# untitled.net
KiCad netlist of a schematic drawn in EAGLE
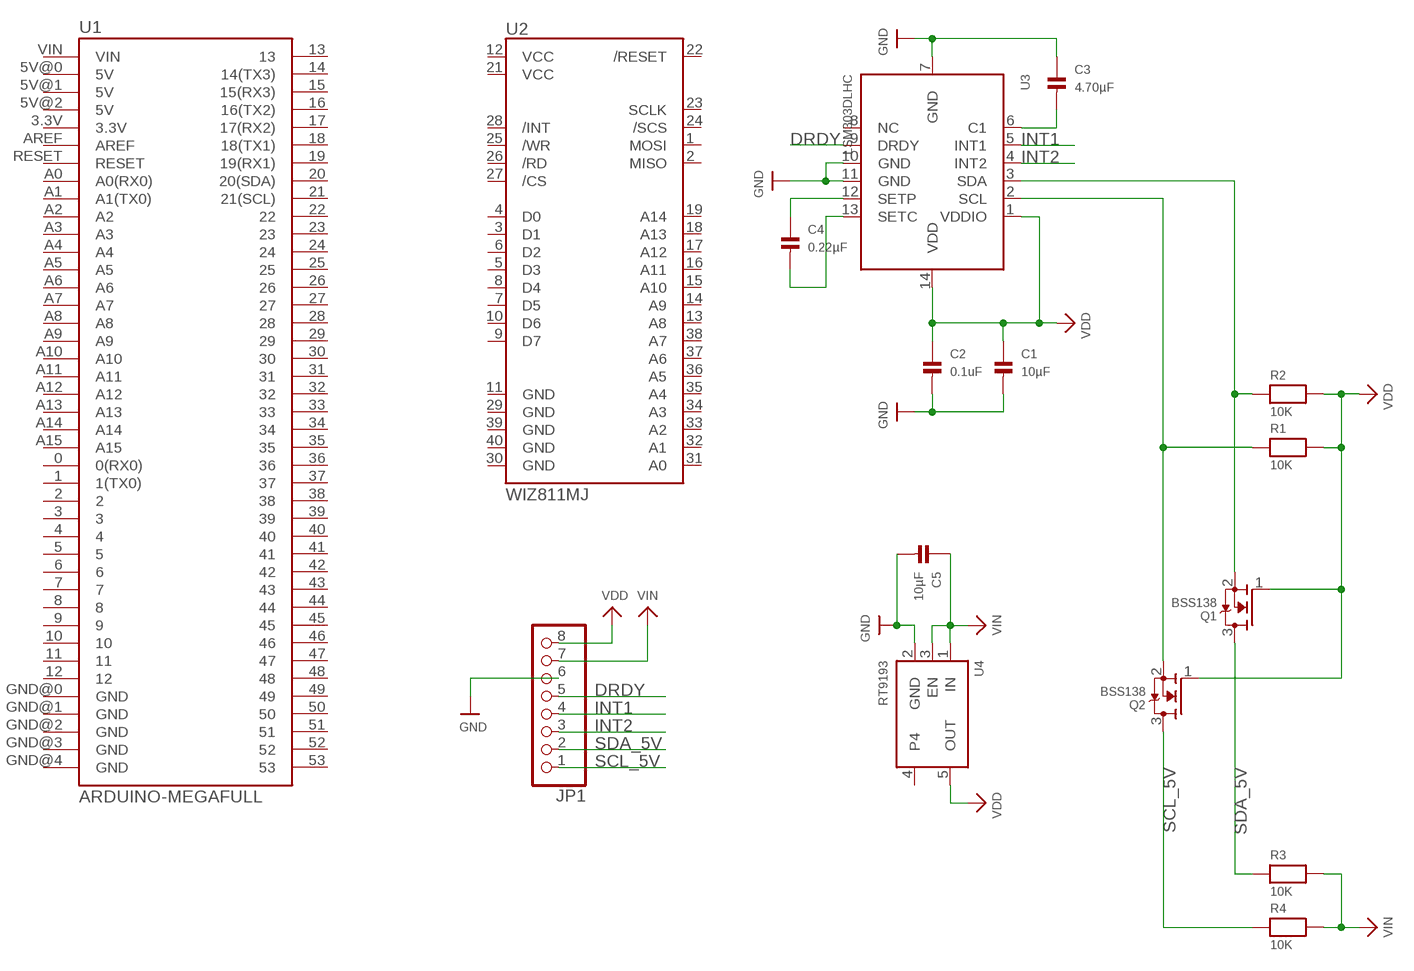
[diagram p0: schematic, sheet 1]

(export (version "E")
  (design (tool "Eeschema 10.0.6"))
  (components
    (comp (ref "C1")
      (value "10µF")
      (footprint "eagle-import:_0805")
      (libsource (lib "eagle-import") (part "CAP_CERAMIC_0805"))
    )
    (comp (ref "C2")
      (value "0.1uF")
      (footprint "eagle-import:_0805")
      (libsource (lib "eagle-import") (part "CAP_CERAMIC_0805"))
    )
    (comp (ref "C3")
      (value "4.70µF")
      (footprint "eagle-import:_0805")
      (libsource (lib "eagle-import") (part "CAP_CERAMIC_0805"))
    )
    (comp (ref "C4")
      (value "0.22µF")
      (footprint "eagle-import:_0805")
      (libsource (lib "eagle-import") (part "CAP_CERAMIC_0805"))
    )
    (comp (ref "C5")
      (value "10µF")
      (footprint "eagle-import:_0805")
      (libsource (lib "eagle-import") (part "CAP_CERAMIC_0805"))
    )
    (comp (ref "JP1")
      (value "HEADER-1X876MIL")
      (footprint "eagle-import:1X08_ROUND_76")
      (libsource (lib "eagle-import") (part "HEADER-1X876MIL"))
    )
    (comp (ref "Q1")
      (value "BSS138")
      (footprint "eagle-import:SOT23-WIDE")
      (libsource (lib "eagle-import") (part "MOSFET-NWIDE"))
    )
    (comp (ref "Q2")
      (value "BSS138")
      (footprint "eagle-import:SOT23-WIDE")
      (libsource (lib "eagle-import") (part "MOSFET-NWIDE"))
    )
    (comp (ref "R1")
      (value "10K")
      (footprint "eagle-import:_0805")
      (libsource (lib "eagle-import") (part "RESISTOR_0805"))
    )
    (comp (ref "R2")
      (value "10K")
      (footprint "eagle-import:_0805")
      (libsource (lib "eagle-import") (part "RESISTOR_0805"))
    )
    (comp (ref "R3")
      (value "10K")
      (footprint "eagle-import:_0805")
      (libsource (lib "eagle-import") (part "RESISTOR_0805"))
    )
    (comp (ref "R4")
      (value "10K")
      (footprint "eagle-import:_0805")
      (libsource (lib "eagle-import") (part "RESISTOR_0805"))
    )
    (comp (ref "U1")
      (value "ARDUINO-MEGAFULL")
      (footprint "eagle-import:ARDUINO_MEGA")
      (libsource (lib "eagle-import") (part "ARDUINO-MEGAFULL"))
    )
    (comp (ref "U2")
      (value "WIZ811MJ")
      (footprint "eagle-import:WIZ811MJ")
      (libsource (lib "eagle-import") (part "WIZ811MJ"))
    )
    (comp (ref "U3")
      (value "LSM303DLHC")
      (footprint "eagle-import:LGA14")
      (libsource (lib "eagle-import") (part "LSM303DLHC"))
    )
    (comp (ref "U4")
      (value "RT9193")
      (footprint "eagle-import:SOT23-5")
      (libsource (lib "eagle-import") (part "VREG_SOT23-5"))
    )
  )
  (nets
    (net (code "1") (name "/DRDY") (class "Default")
      (node (ref "JP1") (pin "5") (pinfunction "5_5") (pintype "passive"))
      (node (ref "U3") (pin "9") (pinfunction "DRDY_9") (pintype "output"))
    )
    (net (code "2") (name "/INT1") (class "Default")
      (node (ref "JP1") (pin "4") (pinfunction "4_4") (pintype "passive"))
      (node (ref "U3") (pin "5") (pinfunction "INT1_5") (pintype "output"))
    )
    (net (code "3") (name "/INT2") (class "Default")
      (node (ref "JP1") (pin "3") (pinfunction "3_3") (pintype "passive"))
      (node (ref "U3") (pin "4") (pinfunction "INT2_4") (pintype "output"))
    )
    (net (code "4") (name "/SCL_5V") (class "Default")
      (node (ref "JP1") (pin "1") (pinfunction "1_1") (pintype "passive"))
      (node (ref "Q2") (pin "3") (pinfunction "D_3") (pintype "bidirectional"))
      (node (ref "R4") (pin "1") (pinfunction "1_1") (pintype "passive"))
    )
    (net (code "5") (name "/SDA_5V") (class "Default")
      (node (ref "JP1") (pin "2") (pinfunction "2_2") (pintype "passive"))
      (node (ref "Q1") (pin "3") (pinfunction "D_3") (pintype "bidirectional"))
      (node (ref "R3") (pin "1") (pinfunction "1_1") (pintype "passive"))
    )
    (net (code "6") (name "GND") (class "Default")
      (node (ref "C1") (pin "2") (pinfunction "P$2_2") (pintype "passive"))
      (node (ref "C2") (pin "2") (pinfunction "P$2_2") (pintype "passive"))
      (node (ref "C3") (pin "1") (pinfunction "P$1_1") (pintype "passive"))
      (node (ref "C5") (pin "2") (pinfunction "P$2_2") (pintype "passive"))
      (node (ref "JP1") (pin "6") (pinfunction "6_6") (pintype "passive"))
      (node (ref "U3") (pin "10") (pinfunction "GND_10") (pintype "power_in"))
      (node (ref "U3") (pin "11") (pinfunction "GND_11") (pintype "power_in"))
      (node (ref "U3") (pin "7") (pinfunction "GND_7") (pintype "power_in"))
      (node (ref "U4") (pin "2") (pinfunction "GND_2") (pintype "bidirectional"))
    )
    (net (code "7") (name "Net-(C3-P$2)") (class "Default")
      (node (ref "C3") (pin "2") (pinfunction "P$2_2") (pintype "passive"))
      (node (ref "U3") (pin "6") (pinfunction "C1_6") (pintype "bidirectional"))
    )
    (net (code "8") (name "Net-(C4-P$1)") (class "Default")
      (node (ref "C4") (pin "1") (pinfunction "P$1_1") (pintype "passive"))
      (node (ref "U3") (pin "12") (pinfunction "SETP_12") (pintype "bidirectional"))
    )
    (net (code "9") (name "Net-(C4-P$2)") (class "Default")
      (node (ref "C4") (pin "2") (pinfunction "P$2_2") (pintype "passive"))
      (node (ref "U3") (pin "13") (pinfunction "SETC_13") (pintype "bidirectional"))
    )
    (net (code "10") (name "Net-(Q1-S)") (class "Default")
      (node (ref "Q1") (pin "2") (pinfunction "S_2") (pintype "bidirectional"))
      (node (ref "R2") (pin "1") (pinfunction "1_1") (pintype "passive"))
      (node (ref "U3") (pin "3") (pinfunction "SDA_3") (pintype "bidirectional"))
    )
    (net (code "11") (name "Net-(Q2-S)") (class "Default")
      (node (ref "Q2") (pin "2") (pinfunction "S_2") (pintype "bidirectional"))
      (node (ref "R1") (pin "1") (pinfunction "1_1") (pintype "passive"))
      (node (ref "U3") (pin "2") (pinfunction "SCL_2") (pintype "bidirectional"))
    )
    (net (code "12") (name "VDD") (class "Default")
      (node (ref "C1") (pin "1") (pinfunction "P$1_1") (pintype "passive"))
      (node (ref "C2") (pin "1") (pinfunction "P$1_1") (pintype "passive"))
      (node (ref "JP1") (pin "8") (pinfunction "8_8") (pintype "passive"))
      (node (ref "Q1") (pin "1") (pinfunction "G_1") (pintype "bidirectional"))
      (node (ref "Q2") (pin "1") (pinfunction "G_1") (pintype "bidirectional"))
      (node (ref "R1") (pin "2") (pinfunction "2_2") (pintype "passive"))
      (node (ref "R2") (pin "2") (pinfunction "2_2") (pintype "passive"))
      (node (ref "U3") (pin "1") (pinfunction "VDDIO_1") (pintype "power_in"))
      (node (ref "U3") (pin "14") (pinfunction "VDD_14") (pintype "power_in"))
      (node (ref "U4") (pin "5") (pinfunction "OUT_5") (pintype "bidirectional"))
    )
    (net (code "13") (name "VIN") (class "Default")
      (node (ref "C5") (pin "1") (pinfunction "P$1_1") (pintype "passive"))
      (node (ref "JP1") (pin "7") (pinfunction "7_7") (pintype "passive"))
      (node (ref "R3") (pin "2") (pinfunction "2_2") (pintype "passive"))
      (node (ref "R4") (pin "2") (pinfunction "2_2") (pintype "passive"))
      (node (ref "U4") (pin "1") (pinfunction "IN_1") (pintype "bidirectional"))
      (node (ref "U4") (pin "3") (pinfunction "EN_3") (pintype "bidirectional"))
    )
    (net (code "14") (name "unconnected-(U1-0(RX0)-Pad0)") (class "Default")
      (node (ref "U1") (pin "0") (pinfunction "0(RX0)_0") (pintype "bidirectional"))
    )
    (net (code "15") (name "unconnected-(U1-1(TX0)-Pad1)") (class "Default")
      (node (ref "U1") (pin "1") (pinfunction "1(TX0)_1") (pintype "bidirectional"))
    )
    (net (code "16") (name "unconnected-(U1-5V-Pad5V@0)") (class "Default")
      (node (ref "U1") (pin "5V@0") (pinfunction "5V_5V@0") (pintype "bidirectional"))
    )
    (net (code "17") (name "unconnected-(U1-5V-Pad5V@1)") (class "Default")
      (node (ref "U1") (pin "5V@1") (pinfunction "5V_5V@1") (pintype "bidirectional"))
    )
    (net (code "18") (name "unconnected-(U1-5V-Pad5V@2)") (class "Default")
      (node (ref "U1") (pin "5V@2") (pinfunction "5V_5V@2") (pintype "bidirectional"))
    )
    (net (code "19") (name "unconnected-(U1-14(TX3)-Pad14)") (class "Default")
      (node (ref "U1") (pin "14") (pinfunction "14(TX3)_14") (pintype "bidirectional"))
    )
    (net (code "20") (name "unconnected-(U1-15(RX3)-Pad15)") (class "Default")
      (node (ref "U1") (pin "15") (pinfunction "15(RX3)_15") (pintype "bidirectional"))
    )
    (net (code "21") (name "unconnected-(U1-16(TX2)-Pad16)") (class "Default")
      (node (ref "U1") (pin "16") (pinfunction "16(TX2)_16") (pintype "bidirectional"))
    )
    (net (code "22") (name "unconnected-(U1-17(RX2)-Pad17)") (class "Default")
      (node (ref "U1") (pin "17") (pinfunction "17(RX2)_17") (pintype "bidirectional"))
    )
    (net (code "23") (name "unconnected-(U1-18(TX1)-Pad18)") (class "Default")
      (node (ref "U1") (pin "18") (pinfunction "18(TX1)_18") (pintype "bidirectional"))
    )
    (net (code "24") (name "unconnected-(U1-19(RX1)-Pad19)") (class "Default")
      (node (ref "U1") (pin "19") (pinfunction "19(RX1)_19") (pintype "bidirectional"))
    )
    (net (code "25") (name "unconnected-(U1-20(SDA)-Pad20)") (class "Default")
      (node (ref "U1") (pin "20") (pinfunction "20(SDA)_20") (pintype "bidirectional"))
    )
    (net (code "26") (name "unconnected-(U1-21(SCL)-Pad21)") (class "Default")
      (node (ref "U1") (pin "21") (pinfunction "21(SCL)_21") (pintype "bidirectional"))
    )
    (net (code "27") (name "unconnected-(U1-A0(RX0)-PadA0)") (class "Default")
      (node (ref "U1") (pin "A0") (pinfunction "A0(RX0)_A0") (pintype "bidirectional"))
    )
    (net (code "28") (name "unconnected-(U1-A1(TX0)-PadA1)") (class "Default")
      (node (ref "U1") (pin "A1") (pinfunction "A1(TX0)_A1") (pintype "bidirectional"))
    )
    (net (code "29") (name "unconnected-(U1-GND-PadGND@0)") (class "Default")
      (node (ref "U1") (pin "GND@0") (pinfunction "GND_GND@0") (pintype "bidirectional"))
    )
    (net (code "30") (name "unconnected-(U1-GND-PadGND@1)") (class "Default")
      (node (ref "U1") (pin "GND@1") (pinfunction "GND_GND@1") (pintype "bidirectional"))
    )
    (net (code "31") (name "unconnected-(U1-GND-PadGND@2)") (class "Default")
      (node (ref "U1") (pin "GND@2") (pinfunction "GND_GND@2") (pintype "bidirectional"))
    )
    (net (code "32") (name "unconnected-(U1-GND-PadGND@3)") (class "Default")
      (node (ref "U1") (pin "GND@3") (pinfunction "GND_GND@3") (pintype "bidirectional"))
    )
    (net (code "33") (name "unconnected-(U1-GND-PadGND@4)") (class "Default")
      (node (ref "U1") (pin "GND@4") (pinfunction "GND_GND@4") (pintype "bidirectional"))
    )
    (net (code "34") (name "unconnected-(U1-Pad2)") (class "Default")
      (node (ref "U1") (pin "2") (pinfunction "2_2") (pintype "bidirectional"))
    )
    (net (code "35") (name "unconnected-(U1-Pad3)") (class "Default")
      (node (ref "U1") (pin "3") (pinfunction "3_3") (pintype "bidirectional"))
    )
    (net (code "36") (name "unconnected-(U1-Pad3.3V)") (class "Default")
      (node (ref "U1") (pin "3.3V") (pinfunction "3.3V_3.3V") (pintype "bidirectional"))
    )
    (net (code "37") (name "unconnected-(U1-Pad4)") (class "Default")
      (node (ref "U1") (pin "4") (pinfunction "4_4") (pintype "bidirectional"))
    )
    (net (code "38") (name "unconnected-(U1-Pad5)") (class "Default")
      (node (ref "U1") (pin "5") (pinfunction "5_5") (pintype "bidirectional"))
    )
    (net (code "39") (name "unconnected-(U1-Pad6)") (class "Default")
      (node (ref "U1") (pin "6") (pinfunction "6_6") (pintype "bidirectional"))
    )
    (net (code "40") (name "unconnected-(U1-Pad7)") (class "Default")
      (node (ref "U1") (pin "7") (pinfunction "7_7") (pintype "bidirectional"))
    )
    (net (code "41") (name "unconnected-(U1-Pad8)") (class "Default")
      (node (ref "U1") (pin "8") (pinfunction "8_8") (pintype "bidirectional"))
    )
    (net (code "42") (name "unconnected-(U1-Pad9)") (class "Default")
      (node (ref "U1") (pin "9") (pinfunction "9_9") (pintype "bidirectional"))
    )
    (net (code "43") (name "unconnected-(U1-Pad10)") (class "Default")
      (node (ref "U1") (pin "10") (pinfunction "10_10") (pintype "bidirectional"))
    )
    (net (code "44") (name "unconnected-(U1-Pad11)") (class "Default")
      (node (ref "U1") (pin "11") (pinfunction "11_11") (pintype "bidirectional"))
    )
    (net (code "45") (name "unconnected-(U1-Pad12)") (class "Default")
      (node (ref "U1") (pin "12") (pinfunction "12_12") (pintype "bidirectional"))
    )
    (net (code "46") (name "unconnected-(U1-Pad13)") (class "Default")
      (node (ref "U1") (pin "13") (pinfunction "13_13") (pintype "bidirectional"))
    )
    (net (code "47") (name "unconnected-(U1-Pad22)") (class "Default")
      (node (ref "U1") (pin "22") (pinfunction "22_22") (pintype "bidirectional"))
    )
    (net (code "48") (name "unconnected-(U1-Pad23)") (class "Default")
      (node (ref "U1") (pin "23") (pinfunction "23_23") (pintype "bidirectional"))
    )
    (net (code "49") (name "unconnected-(U1-Pad24)") (class "Default")
      (node (ref "U1") (pin "24") (pinfunction "24_24") (pintype "bidirectional"))
    )
    (net (code "50") (name "unconnected-(U1-Pad25)") (class "Default")
      (node (ref "U1") (pin "25") (pinfunction "25_25") (pintype "bidirectional"))
    )
    (net (code "51") (name "unconnected-(U1-Pad26)") (class "Default")
      (node (ref "U1") (pin "26") (pinfunction "26_26") (pintype "bidirectional"))
    )
    (net (code "52") (name "unconnected-(U1-Pad27)") (class "Default")
      (node (ref "U1") (pin "27") (pinfunction "27_27") (pintype "bidirectional"))
    )
    (net (code "53") (name "unconnected-(U1-Pad28)") (class "Default")
      (node (ref "U1") (pin "28") (pinfunction "28_28") (pintype "bidirectional"))
    )
    (net (code "54") (name "unconnected-(U1-Pad29)") (class "Default")
      (node (ref "U1") (pin "29") (pinfunction "29_29") (pintype "bidirectional"))
    )
    (net (code "55") (name "unconnected-(U1-Pad30)") (class "Default")
      (node (ref "U1") (pin "30") (pinfunction "30_30") (pintype "bidirectional"))
    )
    (net (code "56") (name "unconnected-(U1-Pad31)") (class "Default")
      (node (ref "U1") (pin "31") (pinfunction "31_31") (pintype "bidirectional"))
    )
    (net (code "57") (name "unconnected-(U1-Pad32)") (class "Default")
      (node (ref "U1") (pin "32") (pinfunction "32_32") (pintype "bidirectional"))
    )
    (net (code "58") (name "unconnected-(U1-Pad33)") (class "Default")
      (node (ref "U1") (pin "33") (pinfunction "33_33") (pintype "bidirectional"))
    )
    (net (code "59") (name "unconnected-(U1-Pad34)") (class "Default")
      (node (ref "U1") (pin "34") (pinfunction "34_34") (pintype "bidirectional"))
    )
    (net (code "60") (name "unconnected-(U1-Pad35)") (class "Default")
      (node (ref "U1") (pin "35") (pinfunction "35_35") (pintype "bidirectional"))
    )
    (net (code "61") (name "unconnected-(U1-Pad36)") (class "Default")
      (node (ref "U1") (pin "36") (pinfunction "36_36") (pintype "bidirectional"))
    )
    (net (code "62") (name "unconnected-(U1-Pad37)") (class "Default")
      (node (ref "U1") (pin "37") (pinfunction "37_37") (pintype "bidirectional"))
    )
    (net (code "63") (name "unconnected-(U1-Pad38)") (class "Default")
      (node (ref "U1") (pin "38") (pinfunction "38_38") (pintype "bidirectional"))
    )
    (net (code "64") (name "unconnected-(U1-Pad39)") (class "Default")
      (node (ref "U1") (pin "39") (pinfunction "39_39") (pintype "bidirectional"))
    )
    (net (code "65") (name "unconnected-(U1-Pad40)") (class "Default")
      (node (ref "U1") (pin "40") (pinfunction "40_40") (pintype "bidirectional"))
    )
    (net (code "66") (name "unconnected-(U1-Pad41)") (class "Default")
      (node (ref "U1") (pin "41") (pinfunction "41_41") (pintype "bidirectional"))
    )
    (net (code "67") (name "unconnected-(U1-Pad42)") (class "Default")
      (node (ref "U1") (pin "42") (pinfunction "42_42") (pintype "bidirectional"))
    )
    (net (code "68") (name "unconnected-(U1-Pad43)") (class "Default")
      (node (ref "U1") (pin "43") (pinfunction "43_43") (pintype "bidirectional"))
    )
    (net (code "69") (name "unconnected-(U1-Pad44)") (class "Default")
      (node (ref "U1") (pin "44") (pinfunction "44_44") (pintype "bidirectional"))
    )
    (net (code "70") (name "unconnected-(U1-Pad45)") (class "Default")
      (node (ref "U1") (pin "45") (pinfunction "45_45") (pintype "bidirectional"))
    )
    (net (code "71") (name "unconnected-(U1-Pad46)") (class "Default")
      (node (ref "U1") (pin "46") (pinfunction "46_46") (pintype "bidirectional"))
    )
    (net (code "72") (name "unconnected-(U1-Pad47)") (class "Default")
      (node (ref "U1") (pin "47") (pinfunction "47_47") (pintype "bidirectional"))
    )
    (net (code "73") (name "unconnected-(U1-Pad48)") (class "Default")
      (node (ref "U1") (pin "48") (pinfunction "48_48") (pintype "bidirectional"))
    )
    (net (code "74") (name "unconnected-(U1-Pad49)") (class "Default")
      (node (ref "U1") (pin "49") (pinfunction "49_49") (pintype "bidirectional"))
    )
    (net (code "75") (name "unconnected-(U1-Pad50)") (class "Default")
      (node (ref "U1") (pin "50") (pinfunction "50_50") (pintype "bidirectional"))
    )
    (net (code "76") (name "unconnected-(U1-Pad51)") (class "Default")
      (node (ref "U1") (pin "51") (pinfunction "51_51") (pintype "bidirectional"))
    )
    (net (code "77") (name "unconnected-(U1-Pad52)") (class "Default")
      (node (ref "U1") (pin "52") (pinfunction "52_52") (pintype "bidirectional"))
    )
    (net (code "78") (name "unconnected-(U1-Pad53)") (class "Default")
      (node (ref "U1") (pin "53") (pinfunction "53_53") (pintype "bidirectional"))
    )
    (net (code "79") (name "unconnected-(U1-PadA2)") (class "Default")
      (node (ref "U1") (pin "A2") (pinfunction "A2_A2") (pintype "bidirectional"))
    )
    (net (code "80") (name "unconnected-(U1-PadA3)") (class "Default")
      (node (ref "U1") (pin "A3") (pinfunction "A3_A3") (pintype "bidirectional"))
    )
    (net (code "81") (name "unconnected-(U1-PadA4)") (class "Default")
      (node (ref "U1") (pin "A4") (pinfunction "A4_A4") (pintype "bidirectional"))
    )
    (net (code "82") (name "unconnected-(U1-PadA5)") (class "Default")
      (node (ref "U1") (pin "A5") (pinfunction "A5_A5") (pintype "bidirectional"))
    )
    (net (code "83") (name "unconnected-(U1-PadA6)") (class "Default")
      (node (ref "U1") (pin "A6") (pinfunction "A6_A6") (pintype "bidirectional"))
    )
    (net (code "84") (name "unconnected-(U1-PadA7)") (class "Default")
      (node (ref "U1") (pin "A7") (pinfunction "A7_A7") (pintype "bidirectional"))
    )
    (net (code "85") (name "unconnected-(U1-PadA8)") (class "Default")
      (node (ref "U1") (pin "A8") (pinfunction "A8_A8") (pintype "bidirectional"))
    )
    (net (code "86") (name "unconnected-(U1-PadA9)") (class "Default")
      (node (ref "U1") (pin "A9") (pinfunction "A9_A9") (pintype "bidirectional"))
    )
    (net (code "87") (name "unconnected-(U1-PadA10)") (class "Default")
      (node (ref "U1") (pin "A10") (pinfunction "A10_A10") (pintype "bidirectional"))
    )
    (net (code "88") (name "unconnected-(U1-PadA11)") (class "Default")
      (node (ref "U1") (pin "A11") (pinfunction "A11_A11") (pintype "bidirectional"))
    )
    (net (code "89") (name "unconnected-(U1-PadA12)") (class "Default")
      (node (ref "U1") (pin "A12") (pinfunction "A12_A12") (pintype "bidirectional"))
    )
    (net (code "90") (name "unconnected-(U1-PadA13)") (class "Default")
      (node (ref "U1") (pin "A13") (pinfunction "A13_A13") (pintype "bidirectional"))
    )
    (net (code "91") (name "unconnected-(U1-PadA14)") (class "Default")
      (node (ref "U1") (pin "A14") (pinfunction "A14_A14") (pintype "bidirectional"))
    )
    (net (code "92") (name "unconnected-(U1-PadA15)") (class "Default")
      (node (ref "U1") (pin "A15") (pinfunction "A15_A15") (pintype "bidirectional"))
    )
    (net (code "93") (name "unconnected-(U1-PadAREF)") (class "Default")
      (node (ref "U1") (pin "AREF") (pinfunction "AREF_AREF") (pintype "bidirectional"))
    )
    (net (code "94") (name "unconnected-(U1-PadRESET)") (class "Default")
      (node (ref "U1") (pin "RESET") (pinfunction "RESET_RESET") (pintype "bidirectional"))
    )
    (net (code "95") (name "unconnected-(U1-PadVIN)") (class "Default")
      (node (ref "U1") (pin "VIN") (pinfunction "VIN_VIN") (pintype "bidirectional"))
    )
    (net (code "96") (name "unconnected-(U2-A0-Pad31)") (class "Default")
      (node (ref "U2") (pin "31") (pinfunction "A0_31") (pintype "bidirectional"))
    )
    (net (code "97") (name "unconnected-(U2-A1-Pad32)") (class "Default")
      (node (ref "U2") (pin "32") (pinfunction "A1_32") (pintype "bidirectional"))
    )
    (net (code "98") (name "unconnected-(U2-A2-Pad33)") (class "Default")
      (node (ref "U2") (pin "33") (pinfunction "A2_33") (pintype "bidirectional"))
    )
    (net (code "99") (name "unconnected-(U2-A3-Pad34)") (class "Default")
      (node (ref "U2") (pin "34") (pinfunction "A3_34") (pintype "bidirectional"))
    )
    (net (code "100") (name "unconnected-(U2-A4-Pad35)") (class "Default")
      (node (ref "U2") (pin "35") (pinfunction "A4_35") (pintype "bidirectional"))
    )
    (net (code "101") (name "unconnected-(U2-A5-Pad36)") (class "Default")
      (node (ref "U2") (pin "36") (pinfunction "A5_36") (pintype "bidirectional"))
    )
    (net (code "102") (name "unconnected-(U2-A6-Pad37)") (class "Default")
      (node (ref "U2") (pin "37") (pinfunction "A6_37") (pintype "bidirectional"))
    )
    (net (code "103") (name "unconnected-(U2-A7-Pad38)") (class "Default")
      (node (ref "U2") (pin "38") (pinfunction "A7_38") (pintype "bidirectional"))
    )
    (net (code "104") (name "unconnected-(U2-A8-Pad13)") (class "Default")
      (node (ref "U2") (pin "13") (pinfunction "A8_13") (pintype "bidirectional"))
    )
    (net (code "105") (name "unconnected-(U2-A9-Pad14)") (class "Default")
      (node (ref "U2") (pin "14") (pinfunction "A9_14") (pintype "bidirectional"))
    )
    (net (code "106") (name "unconnected-(U2-A10-Pad15)") (class "Default")
      (node (ref "U2") (pin "15") (pinfunction "A10_15") (pintype "bidirectional"))
    )
    (net (code "107") (name "unconnected-(U2-A11-Pad16)") (class "Default")
      (node (ref "U2") (pin "16") (pinfunction "A11_16") (pintype "bidirectional"))
    )
    (net (code "108") (name "unconnected-(U2-A12-Pad17)") (class "Default")
      (node (ref "U2") (pin "17") (pinfunction "A12_17") (pintype "bidirectional"))
    )
    (net (code "109") (name "unconnected-(U2-A13-Pad18)") (class "Default")
      (node (ref "U2") (pin "18") (pinfunction "A13_18") (pintype "bidirectional"))
    )
    (net (code "110") (name "unconnected-(U2-A14-Pad19)") (class "Default")
      (node (ref "U2") (pin "19") (pinfunction "A14_19") (pintype "bidirectional"))
    )
    (net (code "111") (name "unconnected-(U2-D0-Pad4)") (class "Default")
      (node (ref "U2") (pin "4") (pinfunction "D0_4") (pintype "bidirectional"))
    )
    (net (code "112") (name "unconnected-(U2-D1-Pad3)") (class "Default")
      (node (ref "U2") (pin "3") (pinfunction "D1_3") (pintype "bidirectional"))
    )
    (net (code "113") (name "unconnected-(U2-D2-Pad6)") (class "Default")
      (node (ref "U2") (pin "6") (pinfunction "D2_6") (pintype "bidirectional"))
    )
    (net (code "114") (name "unconnected-(U2-D3-Pad5)") (class "Default")
      (node (ref "U2") (pin "5") (pinfunction "D3_5") (pintype "bidirectional"))
    )
    (net (code "115") (name "unconnected-(U2-D4-Pad8)") (class "Default")
      (node (ref "U2") (pin "8") (pinfunction "D4_8") (pintype "bidirectional"))
    )
    (net (code "116") (name "unconnected-(U2-D5-Pad7)") (class "Default")
      (node (ref "U2") (pin "7") (pinfunction "D5_7") (pintype "bidirectional"))
    )
    (net (code "117") (name "unconnected-(U2-D6-Pad10)") (class "Default")
      (node (ref "U2") (pin "10") (pinfunction "D6_10") (pintype "bidirectional"))
    )
    (net (code "118") (name "unconnected-(U2-D7-Pad9)") (class "Default")
      (node (ref "U2") (pin "9") (pinfunction "D7_9") (pintype "bidirectional"))
    )
    (net (code "119") (name "unconnected-(U2-GND-Pad11)") (class "Default")
      (node (ref "U2") (pin "11") (pinfunction "GND_11") (pintype "bidirectional"))
    )
    (net (code "120") (name "unconnected-(U2-GND-Pad29)") (class "Default")
      (node (ref "U2") (pin "29") (pinfunction "GND_29") (pintype "bidirectional"))
    )
    (net (code "121") (name "unconnected-(U2-GND-Pad30)") (class "Default")
      (node (ref "U2") (pin "30") (pinfunction "GND_30") (pintype "bidirectional"))
    )
    (net (code "122") (name "unconnected-(U2-GND-Pad39)") (class "Default")
      (node (ref "U2") (pin "39") (pinfunction "GND_39") (pintype "bidirectional"))
    )
    (net (code "123") (name "unconnected-(U2-GND-Pad40)") (class "Default")
      (node (ref "U2") (pin "40") (pinfunction "GND_40") (pintype "bidirectional"))
    )
    (net (code "124") (name "unconnected-(U2-MISO-Pad2)") (class "Default")
      (node (ref "U2") (pin "2") (pinfunction "MISO_2") (pintype "bidirectional"))
    )
    (net (code "125") (name "unconnected-(U2-MOSI-Pad1)") (class "Default")
      (node (ref "U2") (pin "1") (pinfunction "MOSI_1") (pintype "bidirectional"))
    )
    (net (code "126") (name "unconnected-(U2-SCLK-Pad23)") (class "Default")
      (node (ref "U2") (pin "23") (pinfunction "SCLK_23") (pintype "bidirectional"))
    )
    (net (code "127") (name "unconnected-(U2-VCC-Pad12)") (class "Default")
      (node (ref "U2") (pin "12") (pinfunction "VCC_12") (pintype "bidirectional"))
    )
    (net (code "128") (name "unconnected-(U2-VCC-Pad21)") (class "Default")
      (node (ref "U2") (pin "21") (pinfunction "VCC_21") (pintype "bidirectional"))
    )
    (net (code "129") (name "unconnected-(U2-{slash}CS-Pad27)") (class "Default")
      (node (ref "U2") (pin "27") (pinfunction "/CS_27") (pintype "bidirectional"))
    )
    (net (code "130") (name "unconnected-(U2-{slash}INT-Pad28)") (class "Default")
      (node (ref "U2") (pin "28") (pinfunction "/INT_28") (pintype "bidirectional"))
    )
    (net (code "131") (name "unconnected-(U2-{slash}RD-Pad26)") (class "Default")
      (node (ref "U2") (pin "26") (pinfunction "/RD_26") (pintype "bidirectional"))
    )
    (net (code "132") (name "unconnected-(U2-{slash}RESET-Pad22)") (class "Default")
      (node (ref "U2") (pin "22") (pinfunction "/RESET_22") (pintype "bidirectional"))
    )
    (net (code "133") (name "unconnected-(U2-{slash}SCS-Pad24)") (class "Default")
      (node (ref "U2") (pin "24") (pinfunction "/SCS_24") (pintype "bidirectional"))
    )
    (net (code "134") (name "unconnected-(U2-{slash}WR-Pad25)") (class "Default")
      (node (ref "U2") (pin "25") (pinfunction "/WR_25") (pintype "bidirectional"))
    )
    (net (code "135") (name "unconnected-(U3-NC-Pad8)") (class "Default")
      (node (ref "U3") (pin "8") (pinfunction "NC_8") (pintype "bidirectional"))
    )
    (net (code "136") (name "unconnected-(U4-P4-Pad4)") (class "Default")
      (node (ref "U4") (pin "4") (pinfunction "P4_4") (pintype "bidirectional"))
    )
  )
)
